# BlueToothi.net
KiCad netlist of a schematic drawn in Altium Designer
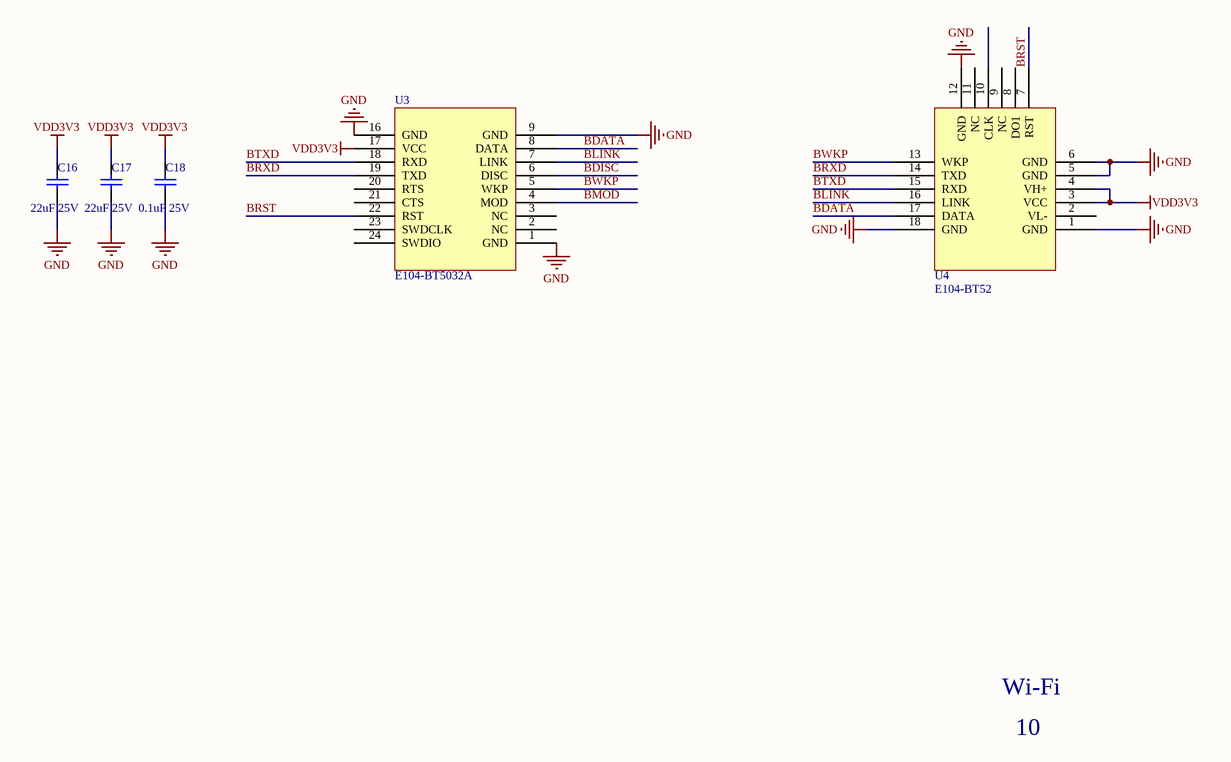
[diagram p0: BlueToothi.SchDoc]

(export (version "E")
  (design (tool "Eeschema 10.0.6"))
  (components
    (comp (ref "C16")
      (value "22uF 25V")
      (footprint "SMD-0805C")
      (description "贴片电容 20%")
      (libsource (lib "XiaoyI") (part "CAP4"))
    )
    (comp (ref "C17")
      (value "22uF 25V")
      (footprint "SMD-0805C")
      (description "贴片电容 20%")
      (libsource (lib "XiaoyI") (part "CAP4"))
    )
    (comp (ref "C18")
      (value "0.1uF 25V")
      (footprint "SMD-0805C")
      (description "贴片电容 20%")
      (libsource (lib "XiaoyI") (part "CAP4"))
    )
    (comp (ref "U3")
      (value "E104-BT5032A")
      (footprint "E104-BT503")
      (description "E104-BT503")
      (libsource (lib "stm32") (part "E104-BT503"))
    )
    (comp (ref "U4") (value "E104-BT52") (footprint "E104-BT52") (libsource (lib "stm32") (part "E104-BT52")))
  )
  (nets
    (net (code "1") (name "/BDATA") (class "Default")
      (node (ref "U3") (pin "8") (pinfunction "DATA_8") (pintype "passive"))
      (node (ref "U4") (pin "17") (pinfunction "DATA_17") (pintype "passive"))
    )
    (net (code "2") (name "/BDISC") (class "Default")
      (node (ref "U3") (pin "6") (pinfunction "DISC_6") (pintype "passive"))
    )
    (net (code "3") (name "/BLINK") (class "Default")
      (node (ref "U3") (pin "7") (pinfunction "LINK_7") (pintype "passive"))
      (node (ref "U4") (pin "16") (pinfunction "LINK_16") (pintype "passive"))
    )
    (net (code "4") (name "/BMOD") (class "Default")
      (node (ref "U3") (pin "4") (pinfunction "MOD_4") (pintype "passive"))
    )
    (net (code "5") (name "/BRST") (class "Default")
      (node (ref "U3") (pin "22") (pinfunction "RST_22") (pintype "passive"))
      (node (ref "U4") (pin "7") (pinfunction "RST_7") (pintype "passive"))
    )
    (net (code "6") (name "/BRXD") (class "Default")
      (node (ref "U3") (pin "19") (pinfunction "TXD_19") (pintype "passive"))
      (node (ref "U4") (pin "14") (pinfunction "TXD_14") (pintype "passive"))
    )
    (net (code "7") (name "/BTXD") (class "Default")
      (node (ref "U3") (pin "18") (pinfunction "RXD_18") (pintype "passive"))
      (node (ref "U4") (pin "15") (pinfunction "RXD_15") (pintype "passive"))
    )
    (net (code "8") (name "/BWKP") (class "Default")
      (node (ref "U3") (pin "5") (pinfunction "WKP_5") (pintype "passive"))
      (node (ref "U4") (pin "13") (pinfunction "WKP_13") (pintype "passive"))
    )
    (net (code "9") (name "GND") (class "Default")
      (node (ref "C16") (pin "1") (pinfunction "1_1") (pintype "passive"))
      (node (ref "C17") (pin "1") (pinfunction "1_1") (pintype "passive"))
      (node (ref "C18") (pin "1") (pinfunction "1_1") (pintype "passive"))
      (node (ref "U3") (pin "1") (pinfunction "GND_1") (pintype "passive"))
      (node (ref "U3") (pin "16") (pinfunction "GND_16") (pintype "passive"))
      (node (ref "U3") (pin "9") (pinfunction "GND_9") (pintype "passive"))
      (node (ref "U4") (pin "1") (pinfunction "GND_1") (pintype "passive"))
      (node (ref "U4") (pin "12") (pinfunction "GND_12") (pintype "passive"))
      (node (ref "U4") (pin "18") (pinfunction "GND_18") (pintype "passive"))
      (node (ref "U4") (pin "5") (pinfunction "GND_5") (pintype "passive"))
      (node (ref "U4") (pin "6") (pinfunction "GND_6") (pintype "passive"))
    )
    (net (code "10") (name "VDD3V3") (class "Default")
      (node (ref "C16") (pin "2") (pinfunction "2_2") (pintype "passive"))
      (node (ref "C17") (pin "2") (pinfunction "2_2") (pintype "passive"))
      (node (ref "C18") (pin "2") (pinfunction "2_2") (pintype "passive"))
      (node (ref "U3") (pin "17") (pinfunction "VCC_17") (pintype "passive"))
      (node (ref "U4") (pin "3") (pinfunction "VCC_3") (pintype "passive"))
      (node (ref "U4") (pin "4") (pinfunction "VH+_4") (pintype "passive"))
    )
    (net (code "11") (name "unconnected-(U3-CTS-Pad21)") (class "Default")
      (node (ref "U3") (pin "21") (pinfunction "CTS_21") (pintype "passive"))
    )
    (net (code "12") (name "unconnected-(U3-NC-Pad2)") (class "Default")
      (node (ref "U3") (pin "2") (pinfunction "NC_2") (pintype "passive"))
    )
    (net (code "13") (name "unconnected-(U3-NC-Pad3)") (class "Default")
      (node (ref "U3") (pin "3") (pinfunction "NC_3") (pintype "passive"))
    )
    (net (code "14") (name "unconnected-(U3-RTS-Pad20)") (class "Default")
      (node (ref "U3") (pin "20") (pinfunction "RTS_20") (pintype "passive"))
    )
    (net (code "15") (name "unconnected-(U3-SWDCLK-Pad23)") (class "Default")
      (node (ref "U3") (pin "23") (pinfunction "SWDCLK_23") (pintype "passive"))
    )
    (net (code "16") (name "unconnected-(U3-SWDIO-Pad24)") (class "Default")
      (node (ref "U3") (pin "24") (pinfunction "SWDIO_24") (pintype "passive"))
    )
    (net (code "17") (name "unconnected-(U4-CLK-Pad10)") (class "Default")
      (node (ref "U4") (pin "10") (pinfunction "CLK_10") (pintype "passive"))
    )
    (net (code "18") (name "unconnected-(U4-DO1-Pad8)") (class "Default")
      (node (ref "U4") (pin "8") (pinfunction "DO1_8") (pintype "passive"))
    )
    (net (code "19") (name "unconnected-(U4-NC-Pad9)") (class "Default")
      (node (ref "U4") (pin "9") (pinfunction "NC_9") (pintype "passive"))
    )
    (net (code "20") (name "unconnected-(U4-NC-Pad11)") (class "Default")
      (node (ref "U4") (pin "11") (pinfunction "NC_11") (pintype "passive"))
    )
    (net (code "21") (name "unconnected-(U4-VL--Pad2)") (class "Default")
      (node (ref "U4") (pin "2") (pinfunction "VL-_2") (pintype "passive"))
    )
  )
)
